# Sheet1.net
KiCad netlist of a schematic drawn in Altium Designer
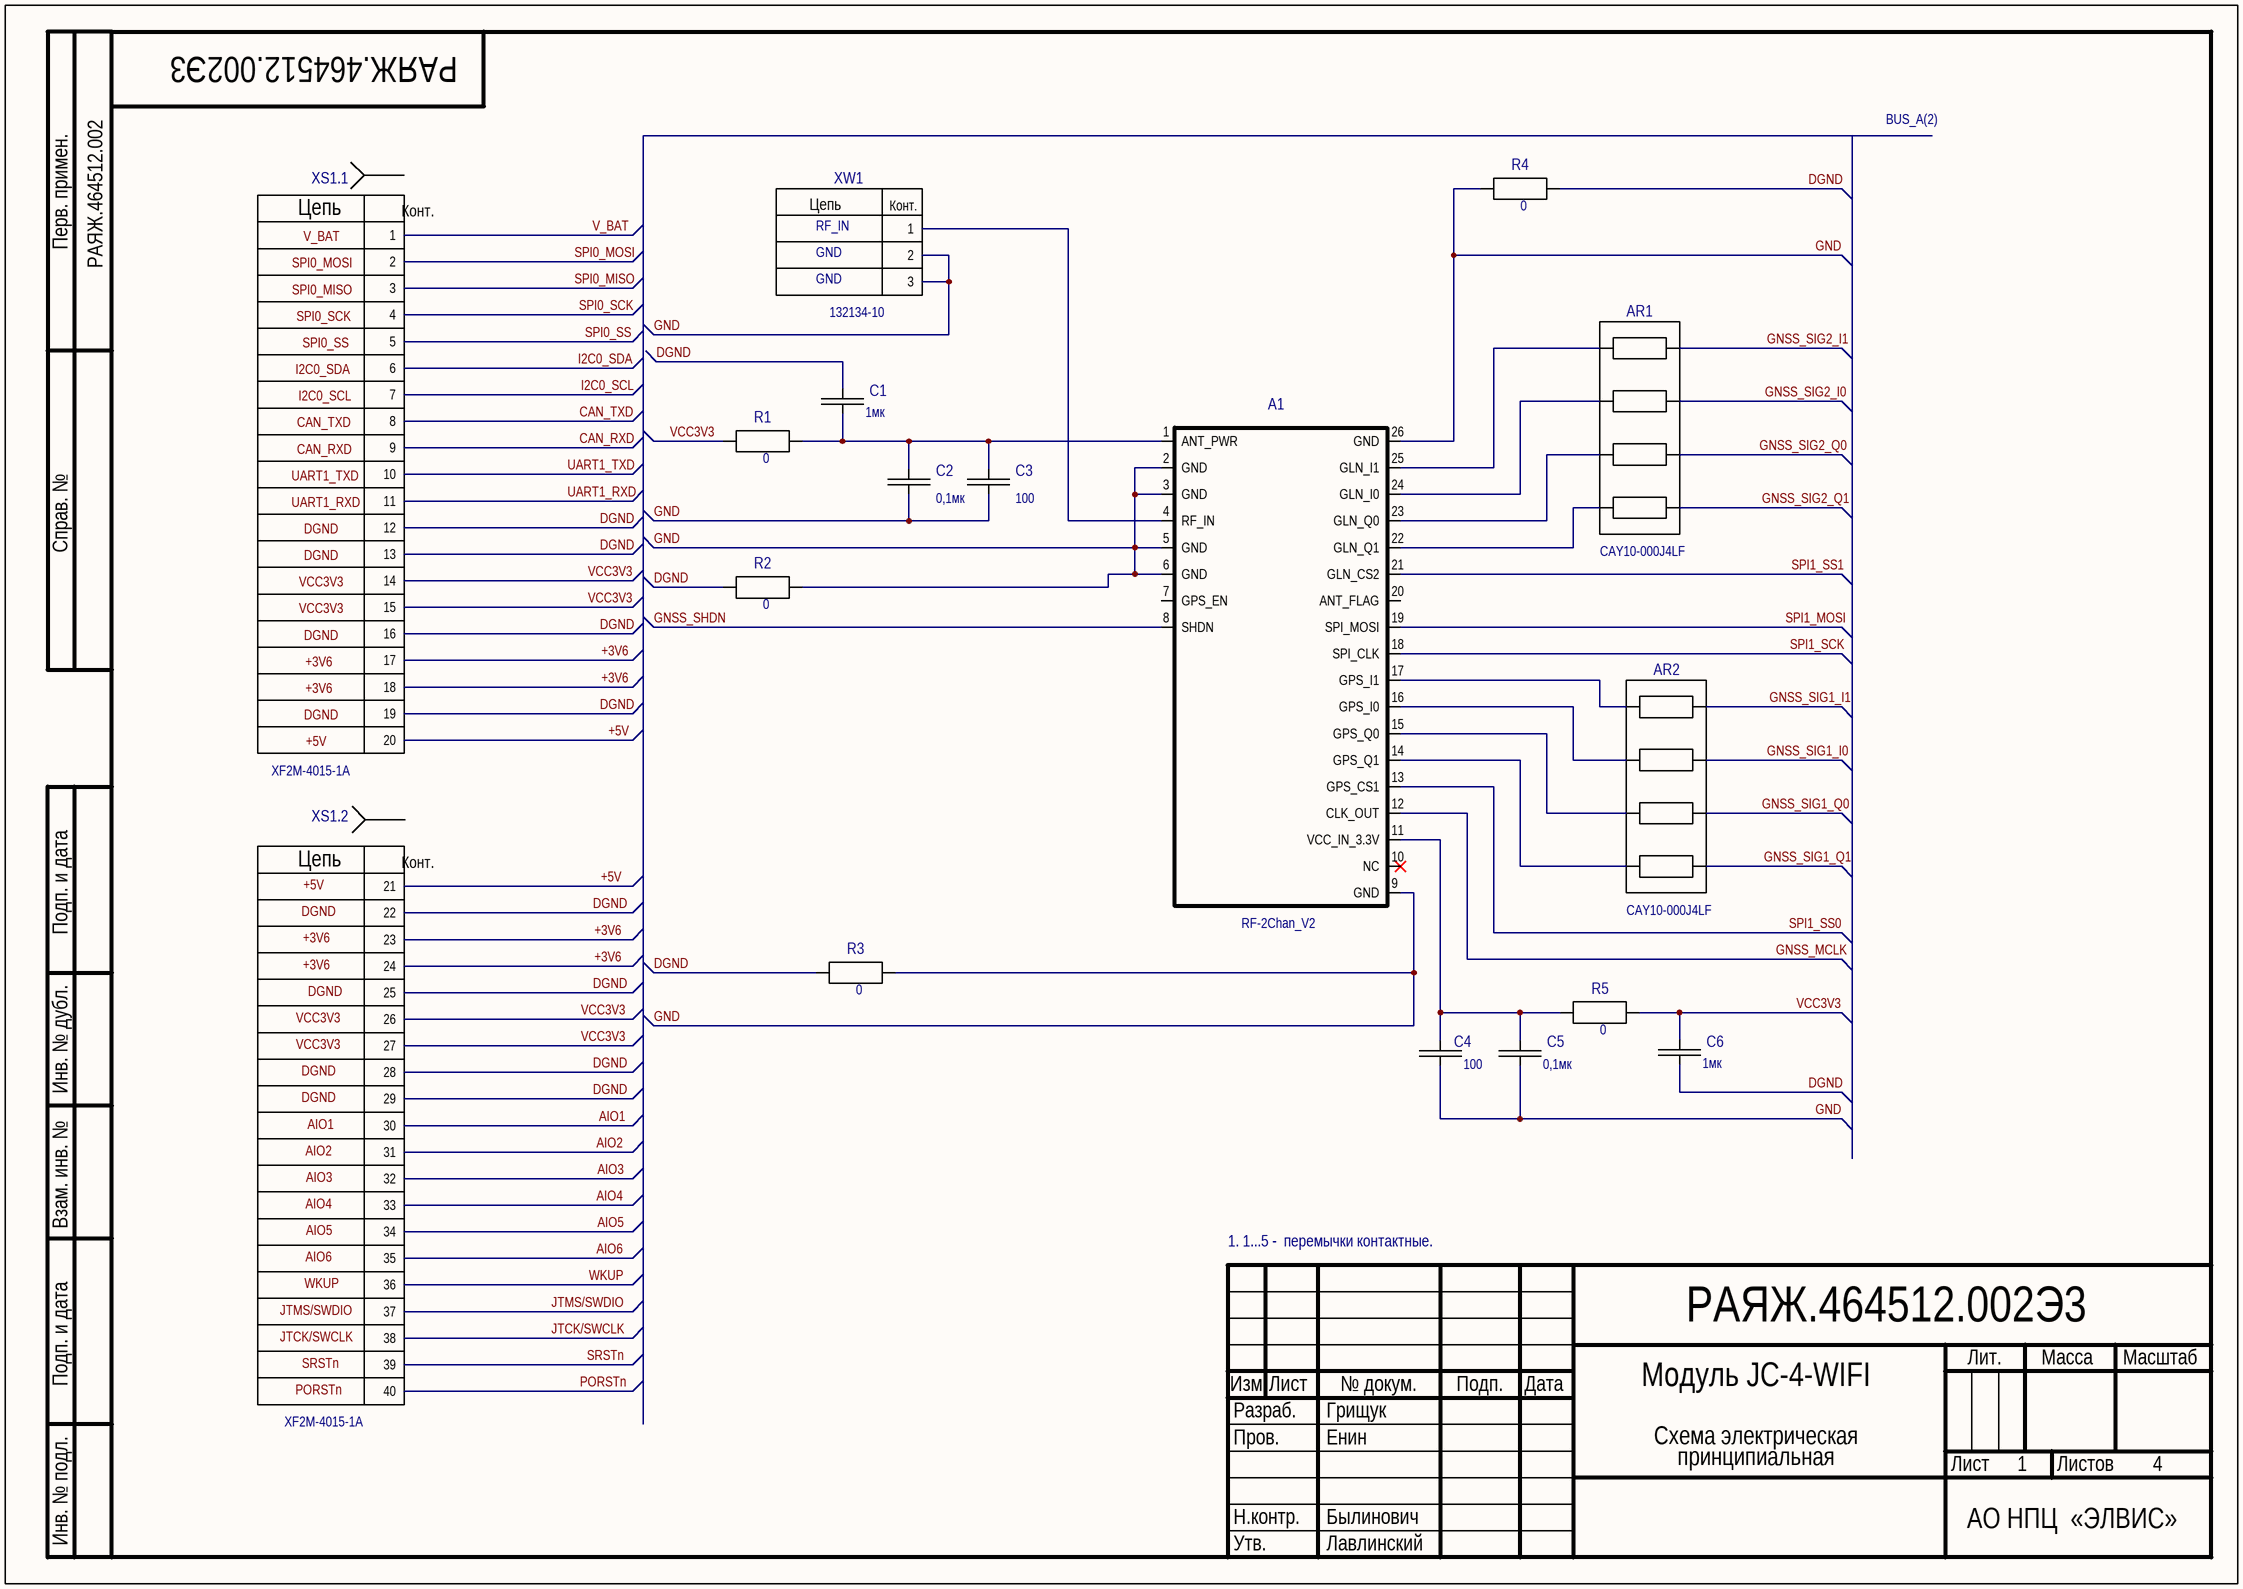
[diagram p0: Sheet1.SchDoc]

(export (version "E")
  (design (tool "Eeschema 10.0.6"))
  (components
    (comp (ref "A1")
      (value "RF-2Chan_V2")
      (footprint "RF-2Chan_V2")
      (libsource (lib "DB") (part "RF-2Chan_V2"))
    )
    (comp (ref "AR1")
      (value "CAY10-000J4LF")
      (footprint "CAY10-xxxJ4")
      (fields (field (name "MANUFACTURER") "ф. Bourns"))
      (libsource (lib "DB") (part "CAY10-xxxJ4"))
    )
    (comp (ref "AR2")
      (value "CAY10-000J4LF")
      (footprint "CAY10-xxxJ4")
      (fields (field (name "MANUFACTURER") "ф. Bourns"))
      (libsource (lib "DB") (part "CAY10-xxxJ4"))
    )
    (comp (ref "C1")
      (value "1мк")
      (footprint "C0402")
      (description "Ceramic Capacitors")
      (fields
        (field (name "PART NUMBER") "C0402 1uF 10V")
        (field (name "MANUFACTURERPARTNUMBER") "GRM153R61A105ME95D")
      )
      (libsource (lib "DB") (part "Capacitor"))
    )
    (comp (ref "C2")
      (value "0,1мк")
      (footprint "C0402")
      (description "Ceramic Capacitors")
      (fields
        (field (name "PART NUMBER") "C0402 0.1uF 16V")
        (field (name "MANUFACTURERPARTNUMBER") "GRM188R61E105KA12D")
      )
      (libsource (lib "DB") (part "Capacitor"))
    )
    (comp (ref "C3")
      (value "100")
      (footprint "C0402")
      (description "Ceramic Capacitors")
      (fields
        (field (name "PART NUMBER") "C0402 100pF")
        (field (name "MANUFACTURERPARTNUMBER") "GRM1555C1H101JA01D")
      )
      (libsource (lib "DB") (part "Capacitor"))
    )
    (comp (ref "C4")
      (value "100")
      (footprint "C0402")
      (description "Ceramic Capacitors")
      (fields
        (field (name "PART NUMBER") "C0402 100pF")
        (field (name "MANUFACTURERPARTNUMBER") "GRM1555C1H101JA01D")
      )
      (libsource (lib "DB") (part "Capacitor"))
    )
    (comp (ref "C5")
      (value "0,1мк")
      (footprint "C0402")
      (description "Ceramic Capacitors")
      (fields
        (field (name "PART NUMBER") "C0402 0.1uF 16V")
        (field (name "MANUFACTURERPARTNUMBER") "GRM188R61E105KA12D")
      )
      (libsource (lib "DB") (part "Capacitor"))
    )
    (comp (ref "C6")
      (value "1мк")
      (footprint "C0402")
      (description "Ceramic Capacitors")
      (fields
        (field (name "PART NUMBER") "C0402 1uF 10V")
        (field (name "MANUFACTURERPARTNUMBER") "GRM153R61A105ME95D")
      )
      (libsource (lib "DB") (part "Capacitor"))
    )
    (comp (ref "R1")
      (value "0")
      (footprint "R0402")
      (description "Резистор")
      (fields (field (name "PART NUMBER") "R0402-0") (field (name "MANUFACTURERPARTNUMBER") "RC0402JR-070RL"))
      (libsource (lib "DB") (part "Resistor"))
    )
    (comp (ref "R2")
      (value "0")
      (footprint "R0402")
      (description "Резистор")
      (fields (field (name "PART NUMBER") "R0402-0") (field (name "MANUFACTURERPARTNUMBER") "RC0402JR-070RL"))
      (libsource (lib "DB") (part "Resistor"))
    )
    (comp (ref "R3")
      (value "0")
      (footprint "R0402")
      (description "Резистор")
      (fields (field (name "PART NUMBER") "R0402-0") (field (name "MANUFACTURERPARTNUMBER") "RC0402JR-070RL"))
      (libsource (lib "DB") (part "Resistor"))
    )
    (comp (ref "R4")
      (value "0")
      (footprint "R0402")
      (description "Резистор")
      (fields (field (name "PART NUMBER") "R0402-0") (field (name "MANUFACTURERPARTNUMBER") "RC0402JR-070RL"))
      (libsource (lib "DB") (part "Resistor"))
    )
    (comp (ref "R5")
      (value "0")
      (footprint "R0402")
      (description "Резистор")
      (fields (field (name "PART NUMBER") "R0402-0") (field (name "MANUFACTURERPARTNUMBER") "RC0402JR-070RL"))
      (libsource (lib "DB") (part "Resistor"))
    )
    (comp (ref "XS1")
      (value "XF2M-4015-1A")
      (footprint "XF2M-4015-1A")
      (description "Rotary Backlock Connector (0.5-mm pitch, Dual Contact)")
      (fields (field (name "MANUFACTURER") "OMRON"))
      (libsource (lib "DB") (part "XF2M-4015-1A"))
    )
    (comp (ref "XW1")
      (value "132134-10")
      (footprint "132134-10")
      (description "Receplacle, SMD")
      (libsource (lib "DB") (part "132134-10"))
    )
  )
  (nets
    (net (code "1") (name "/+3V6") (class "Default")
      (node (ref "XS1") (pin "17") (pinfunction "17_17") (pintype "passive"))
      (node (ref "XS1") (pin "18") (pinfunction "18_18") (pintype "passive"))
      (node (ref "XS1") (pin "23") (pinfunction "23_23") (pintype "passive"))
      (node (ref "XS1") (pin "24") (pinfunction "24_24") (pintype "passive"))
    )
    (net (code "2") (name "/+5V") (class "Default")
      (node (ref "XS1") (pin "20") (pinfunction "20_20") (pintype "passive"))
      (node (ref "XS1") (pin "21") (pinfunction "21_21") (pintype "passive"))
    )
    (net (code "3") (name "/AIO1") (class "Default")
      (node (ref "XS1") (pin "30") (pinfunction "30_30") (pintype "passive"))
    )
    (net (code "4") (name "/AIO2") (class "Default")
      (node (ref "XS1") (pin "31") (pinfunction "31_31") (pintype "passive"))
    )
    (net (code "5") (name "/AIO3") (class "Default")
      (node (ref "XS1") (pin "32") (pinfunction "32_32") (pintype "passive"))
    )
    (net (code "6") (name "/AIO4") (class "Default")
      (node (ref "XS1") (pin "33") (pinfunction "33_33") (pintype "passive"))
    )
    (net (code "7") (name "/AIO5") (class "Default")
      (node (ref "XS1") (pin "34") (pinfunction "34_34") (pintype "passive"))
    )
    (net (code "8") (name "/AIO6") (class "Default")
      (node (ref "XS1") (pin "35") (pinfunction "35_35") (pintype "passive"))
    )
    (net (code "9") (name "/CAN_RXD") (class "Default")
      (node (ref "XS1") (pin "9") (pinfunction "9_9") (pintype "passive"))
    )
    (net (code "10") (name "/CAN_TXD") (class "Default")
      (node (ref "XS1") (pin "8") (pinfunction "8_8") (pintype "passive"))
    )
    (net (code "11") (name "/DGND") (class "Default")
      (node (ref "C1") (pin "1") (pinfunction "1_1") (pintype "passive"))
      (node (ref "C6") (pin "2") (pinfunction "2_2") (pintype "passive"))
      (node (ref "R2") (pin "1") (pinfunction "1_1") (pintype "passive"))
      (node (ref "R3") (pin "1") (pinfunction "1_1") (pintype "passive"))
      (node (ref "R4") (pin "2") (pinfunction "2_2") (pintype "passive"))
      (node (ref "XS1") (pin "12") (pinfunction "12_12") (pintype "passive"))
      (node (ref "XS1") (pin "13") (pinfunction "13_13") (pintype "passive"))
      (node (ref "XS1") (pin "16") (pinfunction "16_16") (pintype "passive"))
      (node (ref "XS1") (pin "19") (pinfunction "19_19") (pintype "passive"))
      (node (ref "XS1") (pin "22") (pinfunction "22_22") (pintype "passive"))
      (node (ref "XS1") (pin "25") (pinfunction "25_25") (pintype "passive"))
      (node (ref "XS1") (pin "28") (pinfunction "28_28") (pintype "passive"))
      (node (ref "XS1") (pin "29") (pinfunction "29_29") (pintype "passive"))
    )
    (net (code "12") (name "/GND") (class "Default")
      (node (ref "A1") (pin "2") (pinfunction "GND_2") (pintype "passive"))
      (node (ref "A1") (pin "26") (pinfunction "GND_26") (pintype "passive"))
      (node (ref "A1") (pin "3") (pinfunction "GND_3") (pintype "passive"))
      (node (ref "A1") (pin "5") (pinfunction "GND_5") (pintype "passive"))
      (node (ref "A1") (pin "6") (pinfunction "GND_6") (pintype "passive"))
      (node (ref "A1") (pin "9") (pinfunction "GND_9") (pintype "passive"))
      (node (ref "C2") (pin "2") (pinfunction "2_2") (pintype "passive"))
      (node (ref "C3") (pin "2") (pinfunction "2_2") (pintype "passive"))
      (node (ref "C4") (pin "2") (pinfunction "2_2") (pintype "passive"))
      (node (ref "C5") (pin "2") (pinfunction "2_2") (pintype "passive"))
      (node (ref "R2") (pin "2") (pinfunction "2_2") (pintype "passive"))
      (node (ref "R3") (pin "2") (pinfunction "2_2") (pintype "passive"))
      (node (ref "R4") (pin "1") (pinfunction "1_1") (pintype "passive"))
      (node (ref "XW1") (pin "2") (pinfunction "2_2") (pintype "passive"))
      (node (ref "XW1") (pin "3") (pinfunction "3_3") (pintype "passive"))
    )
    (net (code "13") (name "/GNSS_MCLK") (class "Default")
      (node (ref "A1") (pin "12") (pinfunction "CLK_OUT_12") (pintype "passive"))
    )
    (net (code "14") (name "/GNSS_SHDN") (class "Default")
      (node (ref "A1") (pin "8") (pinfunction "SHDN_8") (pintype "passive"))
    )
    (net (code "15") (name "/GNSS_SIG1_I0") (class "Default")
      (node (ref "AR2") (pin "7") (pinfunction "7_7") (pintype "passive"))
    )
    (net (code "16") (name "/GNSS_SIG1_I1") (class "Default")
      (node (ref "AR2") (pin "8") (pinfunction "8_8") (pintype "passive"))
    )
    (net (code "17") (name "/GNSS_SIG1_Q0") (class "Default")
      (node (ref "AR2") (pin "6") (pinfunction "6_6") (pintype "passive"))
    )
    (net (code "18") (name "/GNSS_SIG1_Q1") (class "Default")
      (node (ref "AR2") (pin "5") (pinfunction "5_5") (pintype "passive"))
    )
    (net (code "19") (name "/GNSS_SIG2_I0") (class "Default")
      (node (ref "AR1") (pin "7") (pinfunction "7_7") (pintype "passive"))
    )
    (net (code "20") (name "/GNSS_SIG2_I1") (class "Default")
      (node (ref "AR1") (pin "8") (pinfunction "8_8") (pintype "passive"))
    )
    (net (code "21") (name "/GNSS_SIG2_Q0") (class "Default")
      (node (ref "AR1") (pin "6") (pinfunction "6_6") (pintype "passive"))
    )
    (net (code "22") (name "/GNSS_SIG2_Q1") (class "Default")
      (node (ref "AR1") (pin "5") (pinfunction "5_5") (pintype "passive"))
    )
    (net (code "23") (name "/I2C0_SCL") (class "Default")
      (node (ref "XS1") (pin "7") (pinfunction "7_7") (pintype "passive"))
    )
    (net (code "24") (name "/I2C0_SDA") (class "Default")
      (node (ref "XS1") (pin "6") (pinfunction "6_6") (pintype "passive"))
    )
    (net (code "25") (name "/JTCK{slash}SWCLK") (class "Default")
      (node (ref "XS1") (pin "38") (pinfunction "38_38") (pintype "passive"))
    )
    (net (code "26") (name "/JTMS{slash}SWDIO") (class "Default")
      (node (ref "XS1") (pin "37") (pinfunction "37_37") (pintype "passive"))
    )
    (net (code "27") (name "/PORSTn") (class "Default")
      (node (ref "XS1") (pin "40") (pinfunction "40_40") (pintype "passive"))
    )
    (net (code "28") (name "/SPI0_MISO") (class "Default")
      (node (ref "XS1") (pin "3") (pinfunction "3_3") (pintype "passive"))
    )
    (net (code "29") (name "/SPI0_MOSI") (class "Default")
      (node (ref "XS1") (pin "2") (pinfunction "2_2") (pintype "passive"))
    )
    (net (code "30") (name "/SPI0_SCK") (class "Default")
      (node (ref "XS1") (pin "4") (pinfunction "4_4") (pintype "passive"))
    )
    (net (code "31") (name "/SPI0_SS") (class "Default")
      (node (ref "XS1") (pin "5") (pinfunction "5_5") (pintype "passive"))
    )
    (net (code "32") (name "/SPI1_MOSI") (class "Default")
      (node (ref "A1") (pin "19") (pinfunction "SPI_MOSI_19") (pintype "passive"))
    )
    (net (code "33") (name "/SPI1_SCK") (class "Default")
      (node (ref "A1") (pin "18") (pinfunction "SPI_CLK_18") (pintype "passive"))
    )
    (net (code "34") (name "/SPI1_SS0") (class "Default")
      (node (ref "A1") (pin "13") (pinfunction "GPS_CS1_13") (pintype "passive"))
    )
    (net (code "35") (name "/SPI1_SS1") (class "Default")
      (node (ref "A1") (pin "21") (pinfunction "GLN_CS2_21") (pintype "passive"))
    )
    (net (code "36") (name "/SRSTn") (class "Default")
      (node (ref "XS1") (pin "39") (pinfunction "39_39") (pintype "passive"))
    )
    (net (code "37") (name "/UART1_RXD") (class "Default")
      (node (ref "XS1") (pin "11") (pinfunction "11_11") (pintype "passive"))
    )
    (net (code "38") (name "/UART1_TXD") (class "Default")
      (node (ref "XS1") (pin "10") (pinfunction "10_10") (pintype "passive"))
    )
    (net (code "39") (name "/VCC3V3") (class "Default")
      (node (ref "C6") (pin "1") (pinfunction "1_1") (pintype "passive"))
      (node (ref "R1") (pin "1") (pinfunction "1_1") (pintype "passive"))
      (node (ref "R5") (pin "2") (pinfunction "2_2") (pintype "passive"))
      (node (ref "XS1") (pin "14") (pinfunction "14_14") (pintype "passive"))
      (node (ref "XS1") (pin "15") (pinfunction "15_15") (pintype "passive"))
      (node (ref "XS1") (pin "26") (pinfunction "26_26") (pintype "passive"))
      (node (ref "XS1") (pin "27") (pinfunction "27_27") (pintype "passive"))
    )
    (net (code "40") (name "/V_BAT") (class "Default")
      (node (ref "XS1") (pin "1") (pinfunction "1_1") (pintype "passive"))
    )
    (net (code "41") (name "/WKUP") (class "Default")
      (node (ref "XS1") (pin "36") (pinfunction "36_36") (pintype "passive"))
    )
    (net (code "42") (name "Net-(A1-ANT_PWR)") (class "Default")
      (node (ref "A1") (pin "1") (pinfunction "ANT_PWR_1") (pintype "passive"))
      (node (ref "C1") (pin "2") (pinfunction "2_2") (pintype "passive"))
      (node (ref "C2") (pin "1") (pinfunction "1_1") (pintype "passive"))
      (node (ref "C3") (pin "1") (pinfunction "1_1") (pintype "passive"))
      (node (ref "R1") (pin "2") (pinfunction "2_2") (pintype "passive"))
    )
    (net (code "43") (name "Net-(A1-GLN_I0)") (class "Default")
      (node (ref "A1") (pin "24") (pinfunction "GLN_I0_24") (pintype "passive"))
      (node (ref "AR1") (pin "2") (pinfunction "2_2") (pintype "passive"))
    )
    (net (code "44") (name "Net-(A1-GLN_I1)") (class "Default")
      (node (ref "A1") (pin "25") (pinfunction "GLN_I1_25") (pintype "passive"))
      (node (ref "AR1") (pin "1") (pinfunction "1_1") (pintype "passive"))
    )
    (net (code "45") (name "Net-(A1-GLN_Q0)") (class "Default")
      (node (ref "A1") (pin "23") (pinfunction "GLN_Q0_23") (pintype "passive"))
      (node (ref "AR1") (pin "3") (pinfunction "3_3") (pintype "passive"))
    )
    (net (code "46") (name "Net-(A1-GLN_Q1)") (class "Default")
      (node (ref "A1") (pin "22") (pinfunction "GLN_Q1_22") (pintype "passive"))
      (node (ref "AR1") (pin "4") (pinfunction "4_4") (pintype "passive"))
    )
    (net (code "47") (name "Net-(A1-GPS_I0)") (class "Default")
      (node (ref "A1") (pin "16") (pinfunction "GPS_I0_16") (pintype "passive"))
      (node (ref "AR2") (pin "2") (pinfunction "2_2") (pintype "passive"))
    )
    (net (code "48") (name "Net-(A1-GPS_I1)") (class "Default")
      (node (ref "A1") (pin "17") (pinfunction "GPS_I1_17") (pintype "passive"))
      (node (ref "AR2") (pin "1") (pinfunction "1_1") (pintype "passive"))
    )
    (net (code "49") (name "Net-(A1-GPS_Q0)") (class "Default")
      (node (ref "A1") (pin "15") (pinfunction "GPS_Q0_15") (pintype "passive"))
      (node (ref "AR2") (pin "3") (pinfunction "3_3") (pintype "passive"))
    )
    (net (code "50") (name "Net-(A1-GPS_Q1)") (class "Default")
      (node (ref "A1") (pin "14") (pinfunction "GPS_Q1_14") (pintype "passive"))
      (node (ref "AR2") (pin "4") (pinfunction "4_4") (pintype "passive"))
    )
    (net (code "51") (name "Net-(A1-RF_IN)") (class "Default")
      (node (ref "A1") (pin "4") (pinfunction "RF_IN_4") (pintype "passive"))
      (node (ref "XW1") (pin "1") (pinfunction "1_1") (pintype "passive"))
    )
    (net (code "52") (name "Net-(A1-VCC_IN_3.3V)") (class "Default")
      (node (ref "A1") (pin "11") (pinfunction "VCC_IN_3.3V_11") (pintype "passive"))
      (node (ref "C4") (pin "1") (pinfunction "1_1") (pintype "passive"))
      (node (ref "C5") (pin "1") (pinfunction "1_1") (pintype "passive"))
      (node (ref "R5") (pin "1") (pinfunction "1_1") (pintype "passive"))
    )
    (net (code "53") (name "unconnected-(A1-ANT_FLAG-Pad20)") (class "Default")
      (node (ref "A1") (pin "20") (pinfunction "ANT_FLAG_20") (pintype "passive"))
    )
    (net (code "54") (name "unconnected-(A1-GPS_EN-Pad7)") (class "Default")
      (node (ref "A1") (pin "7") (pinfunction "GPS_EN_7") (pintype "passive"))
    )
    (net (code "55") (name "unconnected-(A1-NC-Pad10)") (class "Default")
      (node (ref "A1") (pin "10") (pinfunction "NC_10") (pintype "passive+no_connect"))
    )
  )
)
